# OF1_v1.net
KiCad netlist of a schematic drawn in EAGLE
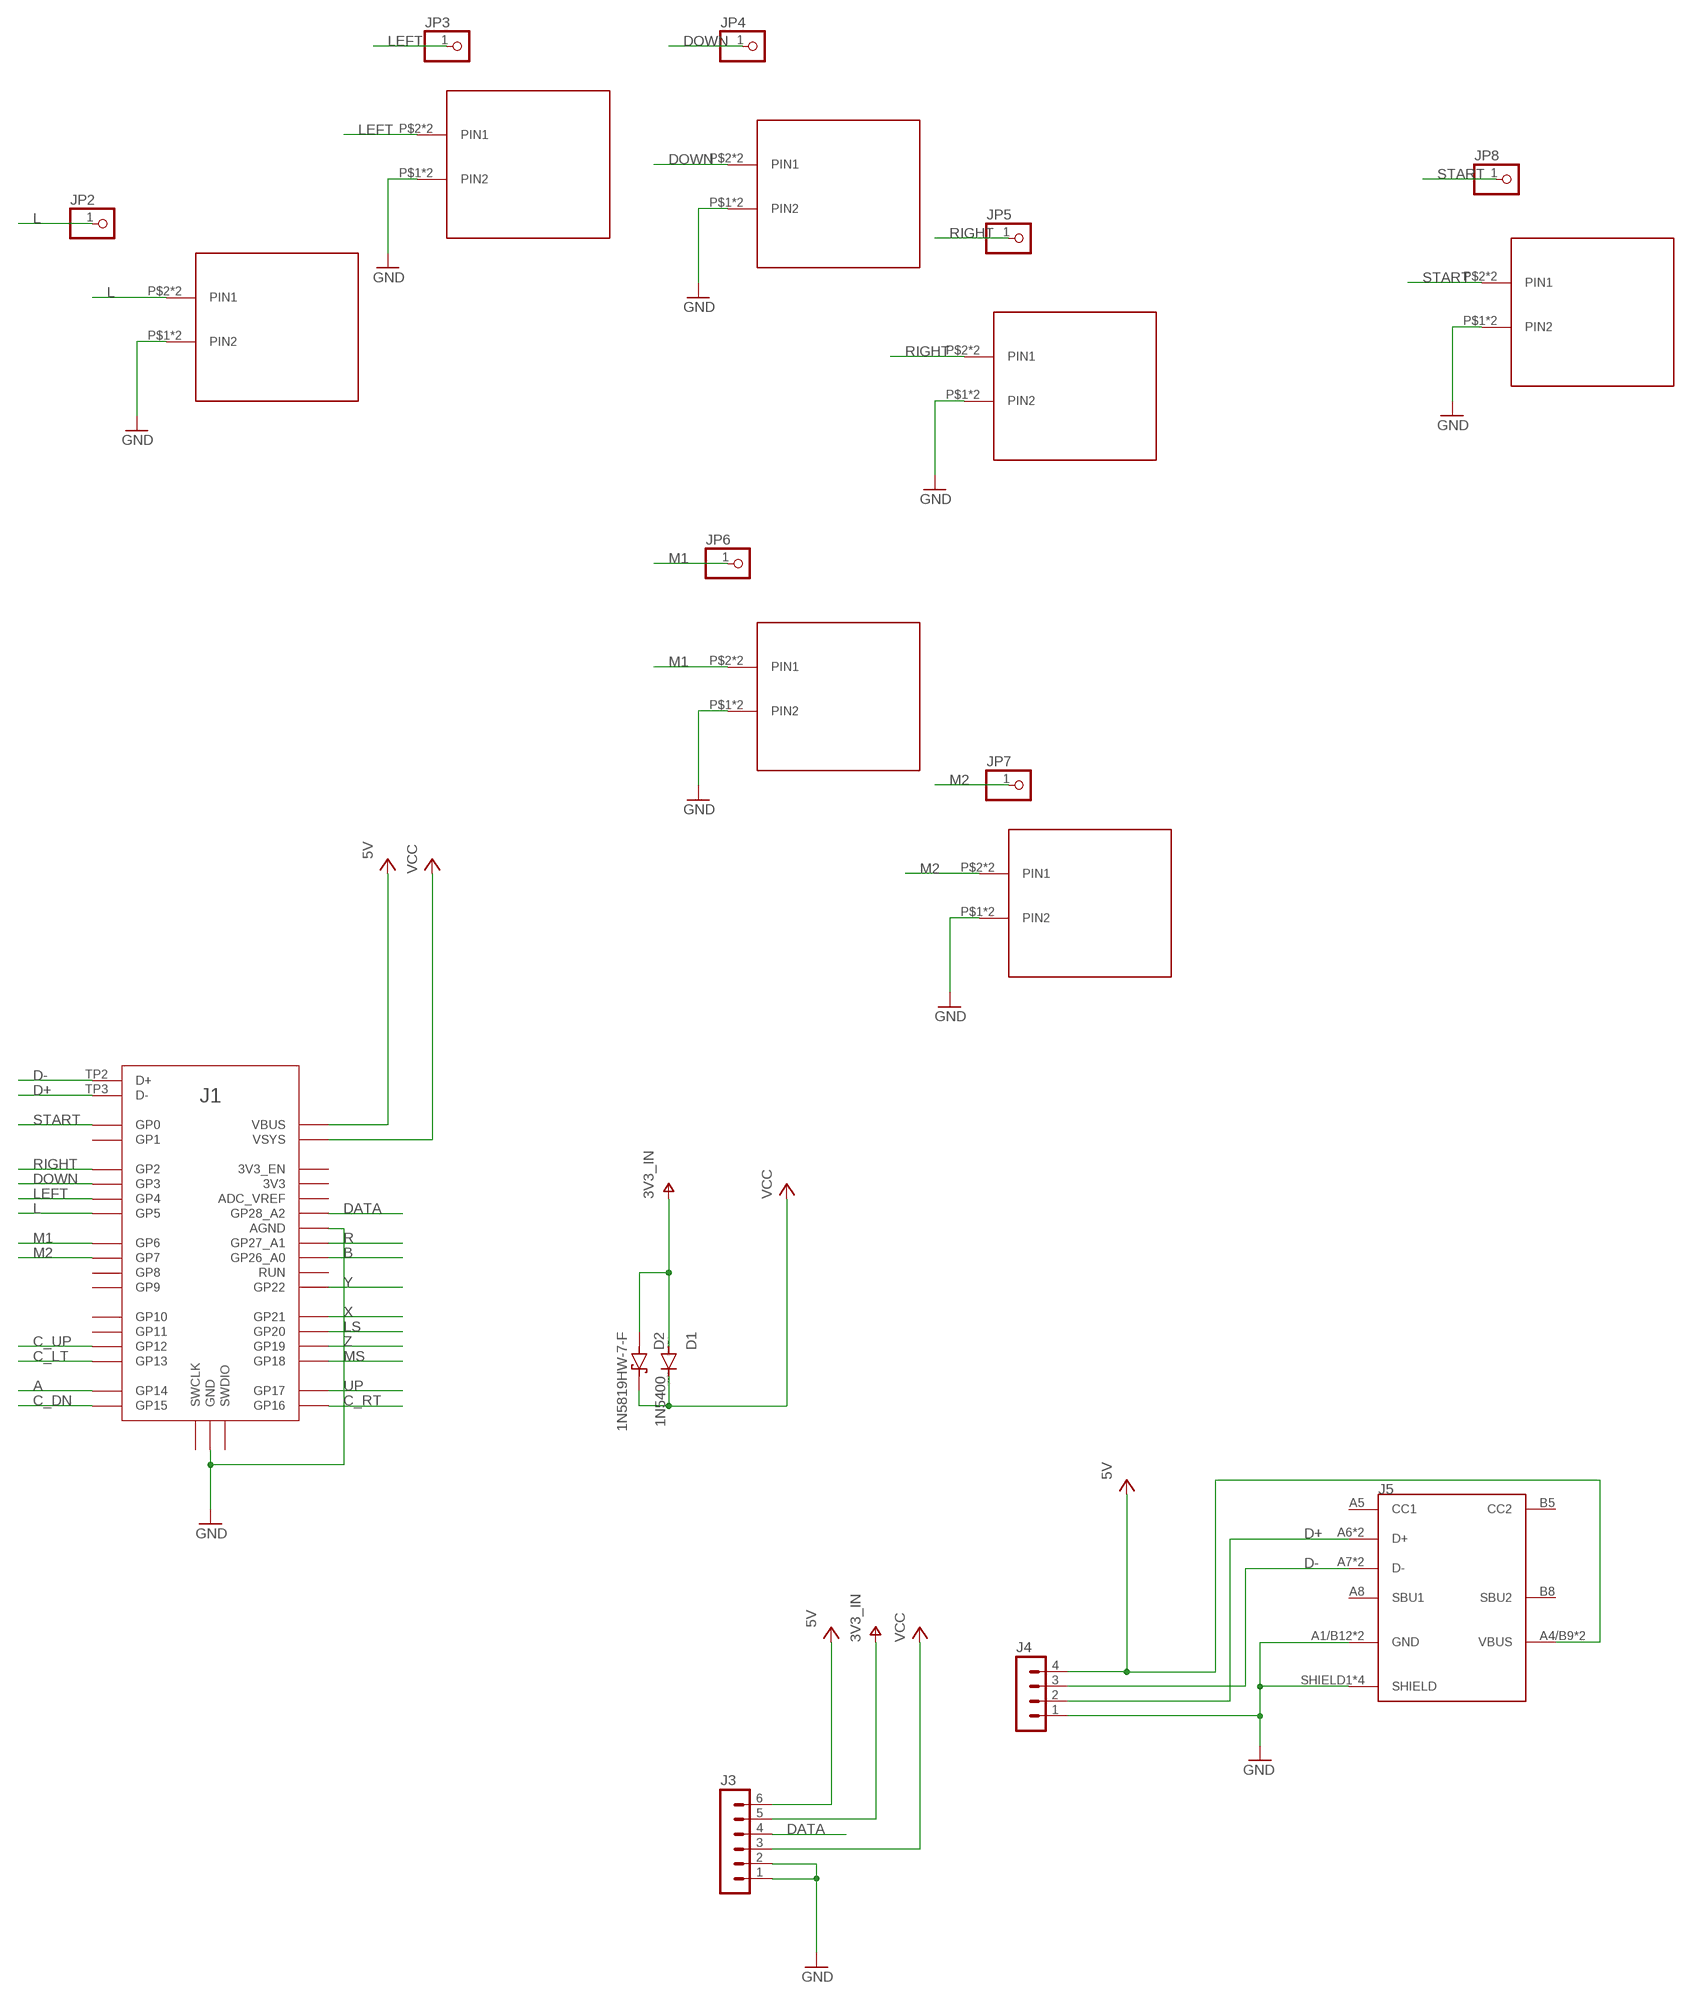
[diagram p0: schematic, sheet 1, part 1 of 2]
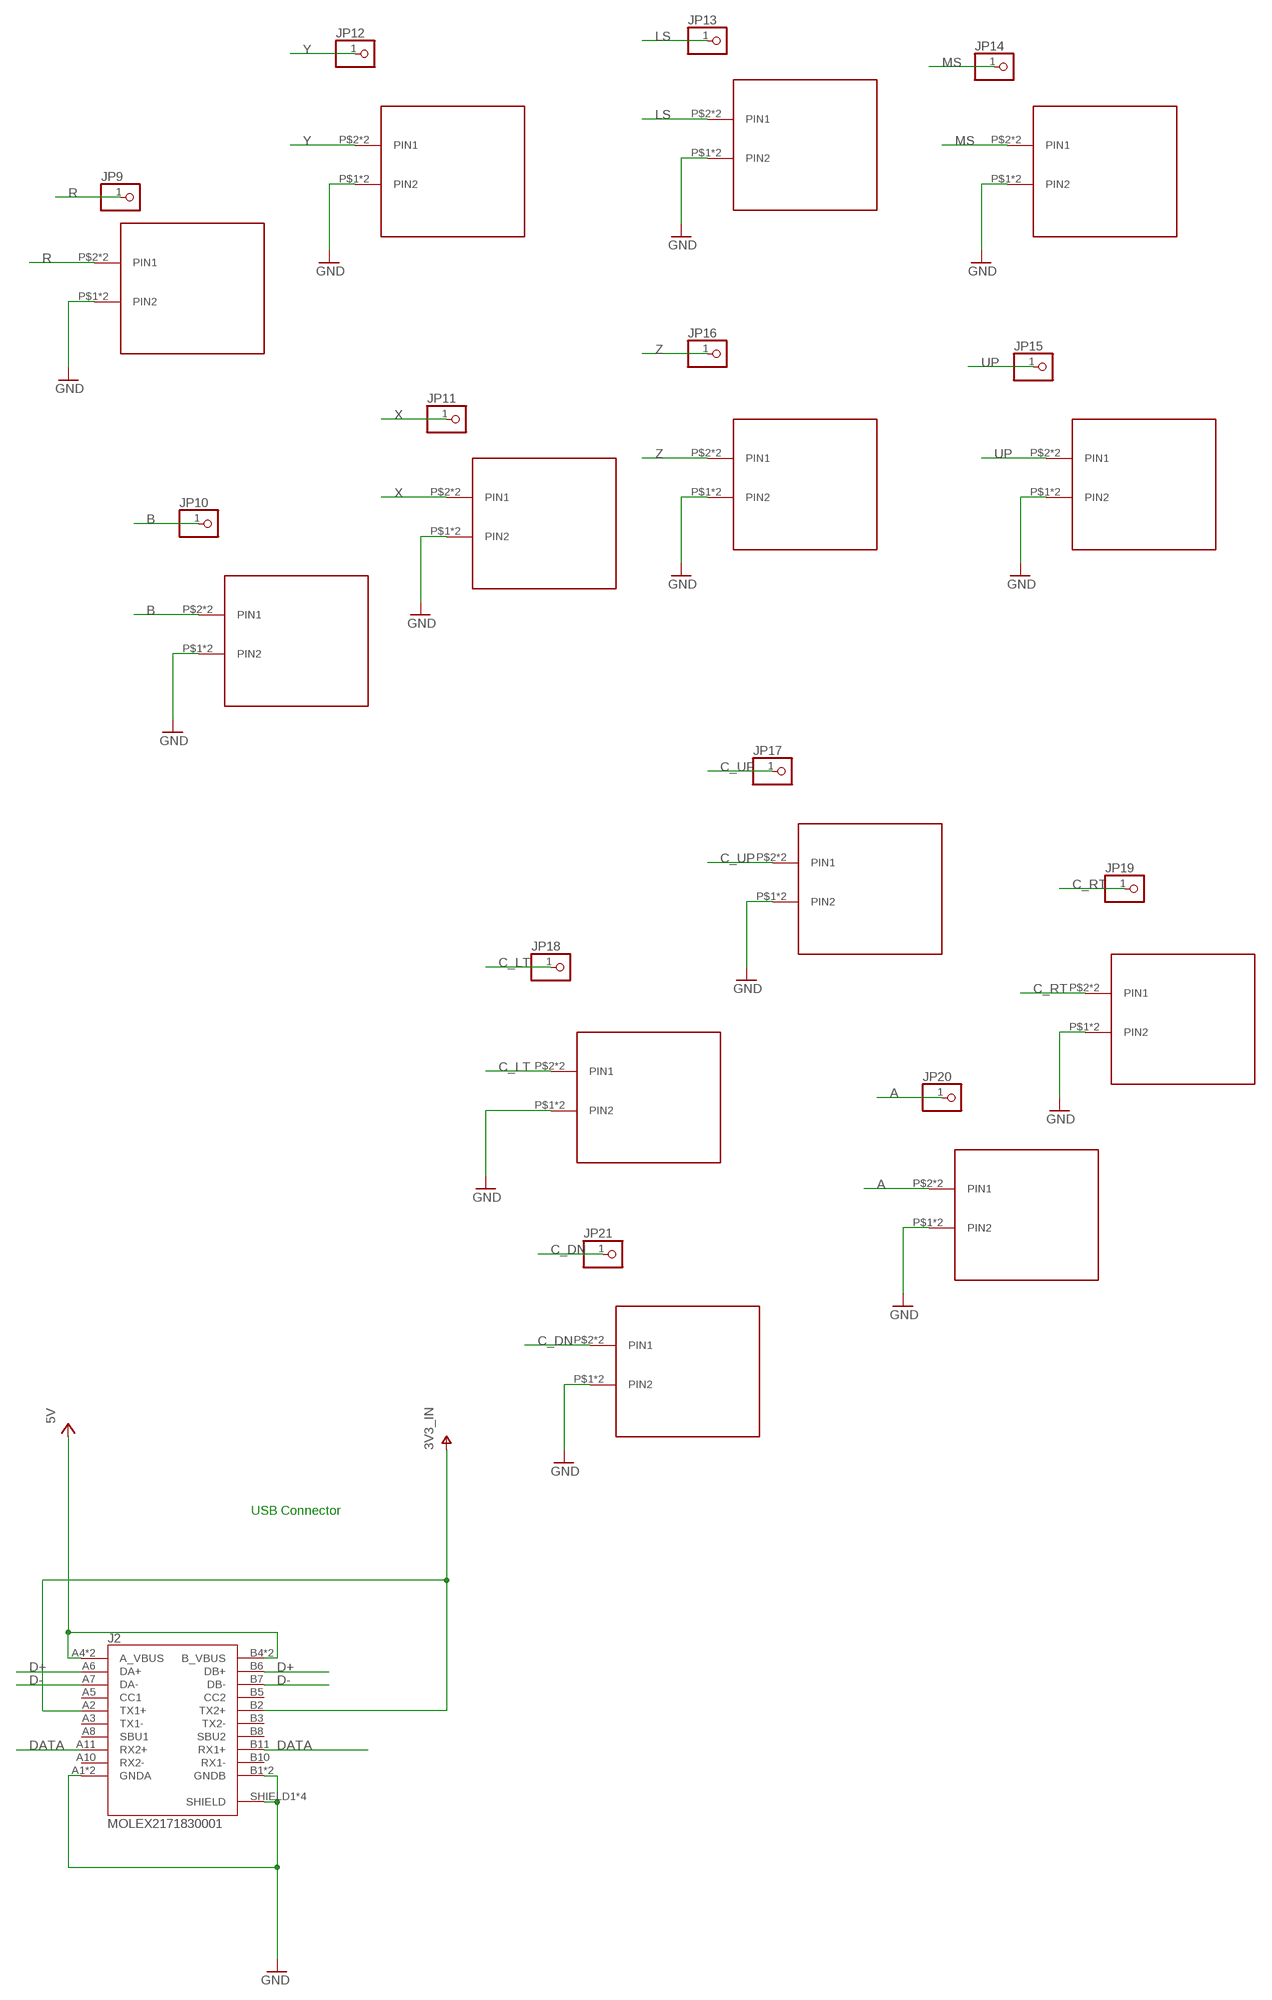
[diagram p1: schematic, sheet 1, part 2 of 2]

(export (version "E")
  (design (tool "Eeschema 10.0.6"))
  (components
    (comp (ref "D1")
      (value "1N5400")
      (footprint "eagle-import:DO201-15")
      (libsource (lib "eagle-import") (part "1N5400"))
    )
    (comp (ref "D2")
      (value "1N5819HW-7-F")
      (footprint "eagle-import:SOD3715X145N")
      (fields (field (name "MF") "Diodes Inc."))
      (libsource (lib "eagle-import") (part "1N5819HW-7-F"))
    )
    (comp (ref "J1")
      (value "RPI_PICO-TH")
      (footprint "eagle-import:RPI_PICO_TH")
      (libsource (lib "eagle-import") (part "RPI_PICO-TH"))
    )
    (comp (ref "J2")
      (value "MOLEX2171830001")
      (footprint "eagle-import:24P")
      (libsource (lib "eagle-import") (part "MOLEX2171830001"))
    )
    (comp (ref "J3")
      (value "MA06-1")
      (footprint "eagle-import:MA06-1")
      (libsource (lib "eagle-import") (part "MA06-1"))
    )
    (comp (ref "J4")
      (value "MA04-1")
      (footprint "eagle-import:MA04-1")
      (libsource (lib "eagle-import") (part "MA04-1"))
    )
    (comp (ref "J5")
      (value "GT-USB-7010ASV")
      (footprint "eagle-import:16P")
      (libsource (lib "eagle-import") (part "GT-USB-7010ASV"))
    )
    (comp (ref "JP2")
      (value "PINHD-1X1")
      (footprint "eagle-import:1X01")
      (libsource (lib "eagle-import") (part "PINHD-1X1"))
    )
    (comp (ref "JP3")
      (value "PINHD-1X1")
      (footprint "eagle-import:1X01")
      (libsource (lib "eagle-import") (part "PINHD-1X1"))
    )
    (comp (ref "JP4")
      (value "PINHD-1X1")
      (footprint "eagle-import:1X01")
      (libsource (lib "eagle-import") (part "PINHD-1X1"))
    )
    (comp (ref "JP5")
      (value "PINHD-1X1")
      (footprint "eagle-import:1X01")
      (libsource (lib "eagle-import") (part "PINHD-1X1"))
    )
    (comp (ref "JP6")
      (value "PINHD-1X1")
      (footprint "eagle-import:1X01")
      (libsource (lib "eagle-import") (part "PINHD-1X1"))
    )
    (comp (ref "JP7")
      (value "PINHD-1X1")
      (footprint "eagle-import:1X01")
      (libsource (lib "eagle-import") (part "PINHD-1X1"))
    )
    (comp (ref "JP8")
      (value "PINHD-1X1")
      (footprint "eagle-import:1X01")
      (libsource (lib "eagle-import") (part "PINHD-1X1"))
    )
    (comp (ref "JP9")
      (value "PINHD-1X1")
      (footprint "eagle-import:1X01")
      (libsource (lib "eagle-import") (part "PINHD-1X1"))
    )
    (comp (ref "JP10")
      (value "PINHD-1X1")
      (footprint "eagle-import:1X01")
      (libsource (lib "eagle-import") (part "PINHD-1X1"))
    )
    (comp (ref "JP11")
      (value "PINHD-1X1")
      (footprint "eagle-import:1X01")
      (libsource (lib "eagle-import") (part "PINHD-1X1"))
    )
    (comp (ref "JP12")
      (value "PINHD-1X1")
      (footprint "eagle-import:1X01")
      (libsource (lib "eagle-import") (part "PINHD-1X1"))
    )
    (comp (ref "JP13")
      (value "PINHD-1X1")
      (footprint "eagle-import:1X01")
      (libsource (lib "eagle-import") (part "PINHD-1X1"))
    )
    (comp (ref "JP14")
      (value "PINHD-1X1")
      (footprint "eagle-import:1X01")
      (libsource (lib "eagle-import") (part "PINHD-1X1"))
    )
    (comp (ref "JP15")
      (value "PINHD-1X1")
      (footprint "eagle-import:1X01")
      (libsource (lib "eagle-import") (part "PINHD-1X1"))
    )
    (comp (ref "JP16")
      (value "PINHD-1X1")
      (footprint "eagle-import:1X01")
      (libsource (lib "eagle-import") (part "PINHD-1X1"))
    )
    (comp (ref "JP17")
      (value "PINHD-1X1")
      (footprint "eagle-import:1X01")
      (libsource (lib "eagle-import") (part "PINHD-1X1"))
    )
    (comp (ref "JP18")
      (value "PINHD-1X1")
      (footprint "eagle-import:1X01")
      (libsource (lib "eagle-import") (part "PINHD-1X1"))
    )
    (comp (ref "JP19")
      (value "PINHD-1X1")
      (footprint "eagle-import:1X01")
      (libsource (lib "eagle-import") (part "PINHD-1X1"))
    )
    (comp (ref "JP20")
      (value "PINHD-1X1")
      (footprint "eagle-import:1X01")
      (libsource (lib "eagle-import") (part "PINHD-1X1"))
    )
    (comp (ref "JP21")
      (value "PINHD-1X1")
      (footprint "eagle-import:1X01")
      (libsource (lib "eagle-import") (part "PINHD-1X1"))
    )
    (comp (ref "U$1")
      (value "MX-B")
      (footprint "eagle-import:MX-BOTH")
      (libsource (lib "eagle-import") (part "MX-B"))
    )
    (comp (ref "U$2")
      (value "MX-B")
      (footprint "eagle-import:MX-BOTH")
      (libsource (lib "eagle-import") (part "MX-B"))
    )
    (comp (ref "U$4")
      (value "MX-B")
      (footprint "eagle-import:MX-BOTH")
      (libsource (lib "eagle-import") (part "MX-B"))
    )
    (comp (ref "U$5")
      (value "MX-B")
      (footprint "eagle-import:MX-BOTH")
      (libsource (lib "eagle-import") (part "MX-B"))
    )
    (comp (ref "U$6")
      (value "MX-B")
      (footprint "eagle-import:MX-BOTH")
      (libsource (lib "eagle-import") (part "MX-B"))
    )
    (comp (ref "U$7")
      (value "MX-B")
      (footprint "eagle-import:MX-BOTH")
      (libsource (lib "eagle-import") (part "MX-B"))
    )
    (comp (ref "U$8")
      (value "MX-B")
      (footprint "eagle-import:MX-BOTH")
      (libsource (lib "eagle-import") (part "MX-B"))
    )
    (comp (ref "U$9")
      (value "MX-B")
      (footprint "eagle-import:MX-BOTH")
      (libsource (lib "eagle-import") (part "MX-B"))
    )
    (comp (ref "U$10")
      (value "MX-B")
      (footprint "eagle-import:MX-BOTH")
      (libsource (lib "eagle-import") (part "MX-B"))
    )
    (comp (ref "U$11")
      (value "MX-B")
      (footprint "eagle-import:MX-BOTH")
      (libsource (lib "eagle-import") (part "MX-B"))
    )
    (comp (ref "U$12")
      (value "MX-B")
      (footprint "eagle-import:MX-BOTH")
      (libsource (lib "eagle-import") (part "MX-B"))
    )
    (comp (ref "U$13")
      (value "MX-B")
      (footprint "eagle-import:MX-BOTH")
      (libsource (lib "eagle-import") (part "MX-B"))
    )
    (comp (ref "U$14")
      (value "MX-B")
      (footprint "eagle-import:MX-BOTH")
      (libsource (lib "eagle-import") (part "MX-B"))
    )
    (comp (ref "U$15")
      (value "MX-B")
      (footprint "eagle-import:MX-BOTH")
      (libsource (lib "eagle-import") (part "MX-B"))
    )
    (comp (ref "U$16")
      (value "MX-B")
      (footprint "eagle-import:MX-BOTH")
      (libsource (lib "eagle-import") (part "MX-B"))
    )
    (comp (ref "U$17")
      (value "MX-B")
      (footprint "eagle-import:MX-BOTH")
      (libsource (lib "eagle-import") (part "MX-B"))
    )
    (comp (ref "U$18")
      (value "MX-B")
      (footprint "eagle-import:MX-BOTH")
      (libsource (lib "eagle-import") (part "MX-B"))
    )
    (comp (ref "U$19")
      (value "MX-B")
      (footprint "eagle-import:MX-BOTH")
      (libsource (lib "eagle-import") (part "MX-B"))
    )
    (comp (ref "U$20")
      (value "MX-B")
      (footprint "eagle-import:MX-BOTH")
      (libsource (lib "eagle-import") (part "MX-B"))
    )
    (comp (ref "U$21")
      (value "MX-B")
      (footprint "eagle-import:MX-BOTH")
      (libsource (lib "eagle-import") (part "MX-B"))
    )
  )
  (nets
    (net (code "1") (name "/A") (class "Default")
      (node (ref "J1") (pin "GP14") (pinfunction "GP14_GP14") (pintype "bidirectional"))
      (node (ref "JP20") (pin "1") (pinfunction "1_1") (pintype "passive"))
      (node (ref "U$20") (pin "P$2") (pinfunction "PIN1_P$2") (pintype "bidirectional"))
      (node (ref "U$20") (pin "P$3") (pinfunction "PIN1_P$3") (pintype "bidirectional"))
    )
    (net (code "2") (name "/B") (class "Default")
      (node (ref "J1") (pin "GP26_A0") (pinfunction "GP26_A0_GP26_A0") (pintype "bidirectional"))
      (node (ref "JP10") (pin "1") (pinfunction "1_1") (pintype "passive"))
      (node (ref "U$13") (pin "P$2") (pinfunction "PIN1_P$2") (pintype "bidirectional"))
      (node (ref "U$13") (pin "P$3") (pinfunction "PIN1_P$3") (pintype "bidirectional"))
    )
    (net (code "3") (name "/C_DN") (class "Default")
      (node (ref "J1") (pin "GP15") (pinfunction "GP15_GP15") (pintype "bidirectional"))
      (node (ref "JP21") (pin "1") (pinfunction "1_1") (pintype "passive"))
      (node (ref "U$21") (pin "P$2") (pinfunction "PIN1_P$2") (pintype "bidirectional"))
      (node (ref "U$21") (pin "P$3") (pinfunction "PIN1_P$3") (pintype "bidirectional"))
    )
    (net (code "4") (name "/C_LT") (class "Default")
      (node (ref "J1") (pin "GP13") (pinfunction "GP13_GP13") (pintype "bidirectional"))
      (node (ref "JP18") (pin "1") (pinfunction "1_1") (pintype "passive"))
      (node (ref "U$18") (pin "P$2") (pinfunction "PIN1_P$2") (pintype "bidirectional"))
      (node (ref "U$18") (pin "P$3") (pinfunction "PIN1_P$3") (pintype "bidirectional"))
    )
    (net (code "5") (name "/C_RT") (class "Default")
      (node (ref "J1") (pin "GP16") (pinfunction "GP16_GP16") (pintype "bidirectional"))
      (node (ref "JP19") (pin "1") (pinfunction "1_1") (pintype "passive"))
      (node (ref "U$19") (pin "P$2") (pinfunction "PIN1_P$2") (pintype "bidirectional"))
      (node (ref "U$19") (pin "P$3") (pinfunction "PIN1_P$3") (pintype "bidirectional"))
    )
    (net (code "6") (name "/C_UP") (class "Default")
      (node (ref "J1") (pin "GP12") (pinfunction "GP12_GP12") (pintype "bidirectional"))
      (node (ref "JP17") (pin "1") (pinfunction "1_1") (pintype "passive"))
      (node (ref "U$17") (pin "P$2") (pinfunction "PIN1_P$2") (pintype "bidirectional"))
      (node (ref "U$17") (pin "P$3") (pinfunction "PIN1_P$3") (pintype "bidirectional"))
    )
    (net (code "7") (name "/D+") (class "Default")
      (node (ref "J1") (pin "TP3") (pinfunction "D-_TP3") (pintype "bidirectional"))
      (node (ref "J2") (pin "A6") (pinfunction "DA+_A6") (pintype "passive"))
      (node (ref "J2") (pin "B6") (pinfunction "DB+_B6") (pintype "passive"))
      (node (ref "J4") (pin "2") (pinfunction "2_2") (pintype "passive"))
      (node (ref "J5") (pin "A6") (pinfunction "D+_A6") (pintype "bidirectional"))
      (node (ref "J5") (pin "B6") (pinfunction "D+_B6") (pintype "bidirectional"))
    )
    (net (code "8") (name "/D-") (class "Default")
      (node (ref "J1") (pin "TP2") (pinfunction "D+_TP2") (pintype "bidirectional"))
      (node (ref "J2") (pin "A7") (pinfunction "DA-_A7") (pintype "passive"))
      (node (ref "J2") (pin "B7") (pinfunction "DB-_B7") (pintype "passive"))
      (node (ref "J4") (pin "3") (pinfunction "3_3") (pintype "passive"))
      (node (ref "J5") (pin "A7") (pinfunction "D-_A7") (pintype "bidirectional"))
      (node (ref "J5") (pin "B7") (pinfunction "D-_B7") (pintype "bidirectional"))
    )
    (net (code "9") (name "/DATA") (class "Default")
      (node (ref "J1") (pin "GP28_A2") (pinfunction "GP28_A2_GP28_A2") (pintype "bidirectional"))
      (node (ref "J2") (pin "A11") (pinfunction "RX2+_A11") (pintype "passive"))
      (node (ref "J2") (pin "B11") (pinfunction "RX1+_B11") (pintype "passive"))
      (node (ref "J3") (pin "4") (pinfunction "4_4") (pintype "passive"))
    )
    (net (code "10") (name "/DOWN") (class "Default")
      (node (ref "J1") (pin "GP3") (pinfunction "GP3_GP3") (pintype "bidirectional"))
      (node (ref "JP4") (pin "1") (pinfunction "1_1") (pintype "passive"))
      (node (ref "U$4") (pin "P$2") (pinfunction "PIN1_P$2") (pintype "bidirectional"))
      (node (ref "U$4") (pin "P$3") (pinfunction "PIN1_P$3") (pintype "bidirectional"))
    )
    (net (code "11") (name "/L") (class "Default")
      (node (ref "J1") (pin "GP5") (pinfunction "GP5_GP5") (pintype "bidirectional"))
      (node (ref "JP2") (pin "1") (pinfunction "1_1") (pintype "passive"))
      (node (ref "U$1") (pin "P$2") (pinfunction "PIN1_P$2") (pintype "bidirectional"))
      (node (ref "U$1") (pin "P$3") (pinfunction "PIN1_P$3") (pintype "bidirectional"))
    )
    (net (code "12") (name "/LEFT") (class "Default")
      (node (ref "J1") (pin "GP4") (pinfunction "GP4_GP4") (pintype "bidirectional"))
      (node (ref "JP3") (pin "1") (pinfunction "1_1") (pintype "passive"))
      (node (ref "U$2") (pin "P$2") (pinfunction "PIN1_P$2") (pintype "bidirectional"))
      (node (ref "U$2") (pin "P$3") (pinfunction "PIN1_P$3") (pintype "bidirectional"))
    )
    (net (code "13") (name "/LS") (class "Default")
      (node (ref "J1") (pin "GP20") (pinfunction "GP20_GP20") (pintype "bidirectional"))
      (node (ref "JP13") (pin "1") (pinfunction "1_1") (pintype "passive"))
      (node (ref "U$11") (pin "P$2") (pinfunction "PIN1_P$2") (pintype "bidirectional"))
      (node (ref "U$11") (pin "P$3") (pinfunction "PIN1_P$3") (pintype "bidirectional"))
    )
    (net (code "14") (name "/M1") (class "Default")
      (node (ref "J1") (pin "GP6") (pinfunction "GP6_GP6") (pintype "bidirectional"))
      (node (ref "JP6") (pin "1") (pinfunction "1_1") (pintype "passive"))
      (node (ref "U$6") (pin "P$2") (pinfunction "PIN1_P$2") (pintype "bidirectional"))
      (node (ref "U$6") (pin "P$3") (pinfunction "PIN1_P$3") (pintype "bidirectional"))
    )
    (net (code "15") (name "/M2") (class "Default")
      (node (ref "J1") (pin "GP7") (pinfunction "GP7_GP7") (pintype "bidirectional"))
      (node (ref "JP7") (pin "1") (pinfunction "1_1") (pintype "passive"))
      (node (ref "U$7") (pin "P$2") (pinfunction "PIN1_P$2") (pintype "bidirectional"))
      (node (ref "U$7") (pin "P$3") (pinfunction "PIN1_P$3") (pintype "bidirectional"))
    )
    (net (code "16") (name "/MS") (class "Default")
      (node (ref "J1") (pin "GP18") (pinfunction "GP18_GP18") (pintype "bidirectional"))
      (node (ref "JP14") (pin "1") (pinfunction "1_1") (pintype "passive"))
      (node (ref "U$12") (pin "P$2") (pinfunction "PIN1_P$2") (pintype "bidirectional"))
      (node (ref "U$12") (pin "P$3") (pinfunction "PIN1_P$3") (pintype "bidirectional"))
    )
    (net (code "17") (name "/R") (class "Default")
      (node (ref "J1") (pin "GP27_A1") (pinfunction "GP27_A1_GP27_A1") (pintype "bidirectional"))
      (node (ref "JP9") (pin "1") (pinfunction "1_1") (pintype "passive"))
      (node (ref "U$9") (pin "P$2") (pinfunction "PIN1_P$2") (pintype "bidirectional"))
      (node (ref "U$9") (pin "P$3") (pinfunction "PIN1_P$3") (pintype "bidirectional"))
    )
    (net (code "18") (name "/RIGHT") (class "Default")
      (node (ref "J1") (pin "GP2") (pinfunction "GP2_GP2") (pintype "bidirectional"))
      (node (ref "JP5") (pin "1") (pinfunction "1_1") (pintype "passive"))
      (node (ref "U$5") (pin "P$2") (pinfunction "PIN1_P$2") (pintype "bidirectional"))
      (node (ref "U$5") (pin "P$3") (pinfunction "PIN1_P$3") (pintype "bidirectional"))
    )
    (net (code "19") (name "/START") (class "Default")
      (node (ref "J1") (pin "GP0") (pinfunction "GP0_GP0") (pintype "bidirectional"))
      (node (ref "JP8") (pin "1") (pinfunction "1_1") (pintype "passive"))
      (node (ref "U$8") (pin "P$2") (pinfunction "PIN1_P$2") (pintype "bidirectional"))
      (node (ref "U$8") (pin "P$3") (pinfunction "PIN1_P$3") (pintype "bidirectional"))
    )
    (net (code "20") (name "/UP") (class "Default")
      (node (ref "J1") (pin "GP17") (pinfunction "GP17_GP17") (pintype "bidirectional"))
      (node (ref "JP15") (pin "1") (pinfunction "1_1") (pintype "passive"))
      (node (ref "U$16") (pin "P$2") (pinfunction "PIN1_P$2") (pintype "bidirectional"))
      (node (ref "U$16") (pin "P$3") (pinfunction "PIN1_P$3") (pintype "bidirectional"))
    )
    (net (code "21") (name "/X") (class "Default")
      (node (ref "J1") (pin "GP21") (pinfunction "GP21_GP21") (pintype "bidirectional"))
      (node (ref "JP11") (pin "1") (pinfunction "1_1") (pintype "passive"))
      (node (ref "U$14") (pin "P$2") (pinfunction "PIN1_P$2") (pintype "bidirectional"))
      (node (ref "U$14") (pin "P$3") (pinfunction "PIN1_P$3") (pintype "bidirectional"))
    )
    (net (code "22") (name "/Y") (class "Default")
      (node (ref "J1") (pin "GP22") (pinfunction "GP22_GP22") (pintype "bidirectional"))
      (node (ref "JP12") (pin "1") (pinfunction "1_1") (pintype "passive"))
      (node (ref "U$10") (pin "P$2") (pinfunction "PIN1_P$2") (pintype "bidirectional"))
      (node (ref "U$10") (pin "P$3") (pinfunction "PIN1_P$3") (pintype "bidirectional"))
    )
    (net (code "23") (name "/Z") (class "Default")
      (node (ref "J1") (pin "GP19") (pinfunction "GP19_GP19") (pintype "bidirectional"))
      (node (ref "JP16") (pin "1") (pinfunction "1_1") (pintype "passive"))
      (node (ref "U$15") (pin "P$2") (pinfunction "PIN1_P$2") (pintype "bidirectional"))
      (node (ref "U$15") (pin "P$3") (pinfunction "PIN1_P$3") (pintype "bidirectional"))
    )
    (net (code "24") (name "3V3_IN") (class "Default")
      (node (ref "D1") (pin "A") (pinfunction "A_A") (pintype "passive"))
      (node (ref "D2") (pin "A") (pinfunction "A_A") (pintype "passive"))
      (node (ref "J2") (pin "A2") (pinfunction "TX1+_A2") (pintype "passive"))
      (node (ref "J2") (pin "B2") (pinfunction "TX2+_B2") (pintype "passive"))
      (node (ref "J3") (pin "5") (pinfunction "5_5") (pintype "passive"))
    )
    (net (code "25") (name "5V") (class "Default")
      (node (ref "J1") (pin "VBUS") (pinfunction "VBUS_VBUS") (pintype "bidirectional"))
      (node (ref "J2") (pin "A4") (pinfunction "A_VBUS_A4") (pintype "passive"))
      (node (ref "J2") (pin "A9") (pinfunction "A_VBUS_A9") (pintype "passive"))
      (node (ref "J2") (pin "B4") (pinfunction "B_VBUS_B4") (pintype "passive"))
      (node (ref "J2") (pin "B9") (pinfunction "B_VBUS_B9") (pintype "passive"))
      (node (ref "J3") (pin "6") (pinfunction "6_6") (pintype "passive"))
      (node (ref "J4") (pin "4") (pinfunction "4_4") (pintype "passive"))
      (node (ref "J5") (pin "A4/B9") (pinfunction "VBUS_A4/B9") (pintype "bidirectional"))
      (node (ref "J5") (pin "B4/A9") (pinfunction "VBUS_B4/A9") (pintype "bidirectional"))
    )
    (net (code "26") (name "GND") (class "Default")
      (node (ref "J1") (pin "AGND") (pinfunction "AGND_AGND") (pintype "bidirectional"))
      (node (ref "J1") (pin "GND@1") (pinfunction "GND_GND@1") (pintype "bidirectional"))
      (node (ref "J1") (pin "GND@2") (pinfunction "GND_GND@2") (pintype "bidirectional"))
      (node (ref "J1") (pin "GND@3") (pinfunction "GND_GND@3") (pintype "bidirectional"))
      (node (ref "J1") (pin "GND@4") (pinfunction "GND_GND@4") (pintype "bidirectional"))
      (node (ref "J1") (pin "GND@5") (pinfunction "GND_GND@5") (pintype "bidirectional"))
      (node (ref "J1") (pin "GND@6") (pinfunction "GND_GND@6") (pintype "bidirectional"))
      (node (ref "J1") (pin "GND@7") (pinfunction "GND_GND@7") (pintype "bidirectional"))
      (node (ref "J1") (pin "GND@8") (pinfunction "GND_GND@8") (pintype "bidirectional"))
      (node (ref "J2") (pin "A1") (pinfunction "GNDA_A1") (pintype "passive"))
      (node (ref "J2") (pin "A12") (pinfunction "GNDA_A12") (pintype "passive"))
      (node (ref "J2") (pin "B1") (pinfunction "GNDB_B1") (pintype "passive"))
      (node (ref "J2") (pin "B12") (pinfunction "GNDB_B12") (pintype "passive"))
      (node (ref "J2") (pin "SHIELD1") (pinfunction "SHIELD_SHIELD1") (pintype "passive"))
      (node (ref "J2") (pin "SHIELD2") (pinfunction "SHIELD_SHIELD2") (pintype "passive"))
      (node (ref "J2") (pin "SHIELD3") (pinfunction "SHIELD_SHIELD3") (pintype "passive"))
      (node (ref "J2") (pin "SHIELD4") (pinfunction "SHIELD_SHIELD4") (pintype "passive"))
      (node (ref "J3") (pin "1") (pinfunction "1_1") (pintype "passive"))
      (node (ref "J3") (pin "2") (pinfunction "2_2") (pintype "passive"))
      (node (ref "J4") (pin "1") (pinfunction "1_1") (pintype "passive"))
      (node (ref "J5") (pin "A1/B12") (pinfunction "GND_A1/B12") (pintype "bidirectional"))
      (node (ref "J5") (pin "B1/A12") (pinfunction "GND_B1/A12") (pintype "bidirectional"))
      (node (ref "J5") (pin "SHIELD1") (pinfunction "SHIELD_SHIELD1") (pintype "bidirectional"))
      (node (ref "J5") (pin "SHIELD2") (pinfunction "SHIELD_SHIELD2") (pintype "bidirectional"))
      (node (ref "J5") (pin "SHIELD3") (pinfunction "SHIELD_SHIELD3") (pintype "bidirectional"))
      (node (ref "J5") (pin "SHIELD4") (pinfunction "SHIELD_SHIELD4") (pintype "bidirectional"))
      (node (ref "U$1") (pin "P$1") (pinfunction "PIN2_P$1") (pintype "bidirectional"))
      (node (ref "U$1") (pin "P$4") (pinfunction "PIN2_P$4") (pintype "bidirectional"))
      (node (ref "U$10") (pin "P$1") (pinfunction "PIN2_P$1") (pintype "bidirectional"))
      (node (ref "U$10") (pin "P$4") (pinfunction "PIN2_P$4") (pintype "bidirectional"))
      (node (ref "U$11") (pin "P$1") (pinfunction "PIN2_P$1") (pintype "bidirectional"))
      (node (ref "U$11") (pin "P$4") (pinfunction "PIN2_P$4") (pintype "bidirectional"))
      (node (ref "U$12") (pin "P$1") (pinfunction "PIN2_P$1") (pintype "bidirectional"))
      (node (ref "U$12") (pin "P$4") (pinfunction "PIN2_P$4") (pintype "bidirectional"))
      (node (ref "U$13") (pin "P$1") (pinfunction "PIN2_P$1") (pintype "bidirectional"))
      (node (ref "U$13") (pin "P$4") (pinfunction "PIN2_P$4") (pintype "bidirectional"))
      (node (ref "U$14") (pin "P$1") (pinfunction "PIN2_P$1") (pintype "bidirectional"))
      (node (ref "U$14") (pin "P$4") (pinfunction "PIN2_P$4") (pintype "bidirectional"))
      (node (ref "U$15") (pin "P$1") (pinfunction "PIN2_P$1") (pintype "bidirectional"))
      (node (ref "U$15") (pin "P$4") (pinfunction "PIN2_P$4") (pintype "bidirectional"))
      (node (ref "U$16") (pin "P$1") (pinfunction "PIN2_P$1") (pintype "bidirectional"))
      (node (ref "U$16") (pin "P$4") (pinfunction "PIN2_P$4") (pintype "bidirectional"))
      (node (ref "U$17") (pin "P$1") (pinfunction "PIN2_P$1") (pintype "bidirectional"))
      (node (ref "U$17") (pin "P$4") (pinfunction "PIN2_P$4") (pintype "bidirectional"))
      (node (ref "U$18") (pin "P$1") (pinfunction "PIN2_P$1") (pintype "bidirectional"))
      (node (ref "U$18") (pin "P$4") (pinfunction "PIN2_P$4") (pintype "bidirectional"))
      (node (ref "U$19") (pin "P$1") (pinfunction "PIN2_P$1") (pintype "bidirectional"))
      (node (ref "U$19") (pin "P$4") (pinfunction "PIN2_P$4") (pintype "bidirectional"))
      (node (ref "U$2") (pin "P$1") (pinfunction "PIN2_P$1") (pintype "bidirectional"))
      (node (ref "U$2") (pin "P$4") (pinfunction "PIN2_P$4") (pintype "bidirectional"))
      (node (ref "U$20") (pin "P$1") (pinfunction "PIN2_P$1") (pintype "bidirectional"))
      (node (ref "U$20") (pin "P$4") (pinfunction "PIN2_P$4") (pintype "bidirectional"))
      (node (ref "U$21") (pin "P$1") (pinfunction "PIN2_P$1") (pintype "bidirectional"))
      (node (ref "U$21") (pin "P$4") (pinfunction "PIN2_P$4") (pintype "bidirectional"))
      (node (ref "U$4") (pin "P$1") (pinfunction "PIN2_P$1") (pintype "bidirectional"))
      (node (ref "U$4") (pin "P$4") (pinfunction "PIN2_P$4") (pintype "bidirectional"))
      (node (ref "U$5") (pin "P$1") (pinfunction "PIN2_P$1") (pintype "bidirectional"))
      (node (ref "U$5") (pin "P$4") (pinfunction "PIN2_P$4") (pintype "bidirectional"))
      (node (ref "U$6") (pin "P$1") (pinfunction "PIN2_P$1") (pintype "bidirectional"))
      (node (ref "U$6") (pin "P$4") (pinfunction "PIN2_P$4") (pintype "bidirectional"))
      (node (ref "U$7") (pin "P$1") (pinfunction "PIN2_P$1") (pintype "bidirectional"))
      (node (ref "U$7") (pin "P$4") (pinfunction "PIN2_P$4") (pintype "bidirectional"))
      (node (ref "U$8") (pin "P$1") (pinfunction "PIN2_P$1") (pintype "bidirectional"))
      (node (ref "U$8") (pin "P$4") (pinfunction "PIN2_P$4") (pintype "bidirectional"))
      (node (ref "U$9") (pin "P$1") (pinfunction "PIN2_P$1") (pintype "bidirectional"))
      (node (ref "U$9") (pin "P$4") (pinfunction "PIN2_P$4") (pintype "bidirectional"))
    )
    (net (code "27") (name "VCC") (class "Default")
      (node (ref "D1") (pin "C") (pinfunction "C_C") (pintype "passive"))
      (node (ref "D2") (pin "C") (pinfunction "K_C") (pintype "passive"))
      (node (ref "J1") (pin "VSYS") (pinfunction "VSYS_VSYS") (pintype "bidirectional"))
      (node (ref "J3") (pin "3") (pinfunction "3_3") (pintype "passive"))
    )
    (net (code "28") (name "unconnected-(J1-Pad3V3)") (class "Default")
      (node (ref "J1") (pin "3V3") (pinfunction "3V3_3V3") (pintype "bidirectional"))
    )
    (net (code "29") (name "unconnected-(J1-Pad3V3_EN)") (class "Default")
      (node (ref "J1") (pin "3V3_EN") (pinfunction "3V3_EN_3V3_EN") (pintype "bidirectional"))
    )
    (net (code "30") (name "unconnected-(J1-PadADC_VREF)") (class "Default")
      (node (ref "J1") (pin "ADC_VREF") (pinfunction "ADC_VREF_ADC_VREF") (pintype "bidirectional"))
    )
    (net (code "31") (name "unconnected-(J1-PadGP1)") (class "Default")
      (node (ref "J1") (pin "GP1") (pinfunction "GP1_GP1") (pintype "bidirectional"))
    )
    (net (code "32") (name "unconnected-(J1-PadGP8)") (class "Default")
      (node (ref "J1") (pin "GP8") (pinfunction "GP8_GP8") (pintype "bidirectional"))
    )
    (net (code "33") (name "unconnected-(J1-PadGP9)") (class "Default")
      (node (ref "J1") (pin "GP9") (pinfunction "GP9_GP9") (pintype "bidirectional"))
    )
    (net (code "34") (name "unconnected-(J1-PadGP10)") (class "Default")
      (node (ref "J1") (pin "GP10") (pinfunction "GP10_GP10") (pintype "bidirectional"))
    )
    (net (code "35") (name "unconnected-(J1-PadGP11)") (class "Default")
      (node (ref "J1") (pin "GP11") (pinfunction "GP11_GP11") (pintype "bidirectional"))
    )
    (net (code "36") (name "unconnected-(J1-PadRUN)") (class "Default")
      (node (ref "J1") (pin "RUN") (pinfunction "RUN_RUN") (pintype "bidirectional"))
    )
    (net (code "37") (name "unconnected-(J1-PadSWCLK)") (class "Default")
      (node (ref "J1") (pin "SWCLK") (pinfunction "SWCLK_SWCLK") (pintype "bidirectional"))
    )
    (net (code "38") (name "unconnected-(J1-PadSWDIO)") (class "Default")
      (node (ref "J1") (pin "SWDIO") (pinfunction "SWDIO_SWDIO") (pintype "bidirectional"))
    )
    (net (code "39") (name "unconnected-(J2-CC1-PadA5)") (class "Default")
      (node (ref "J2") (pin "A5") (pinfunction "CC1_A5") (pintype "passive"))
    )
    (net (code "40") (name "unconnected-(J2-CC2-PadB5)") (class "Default")
      (node (ref "J2") (pin "B5") (pinfunction "CC2_B5") (pintype "passive"))
    )
    (net (code "41") (name "unconnected-(J2-RX1--PadB10)") (class "Default")
      (node (ref "J2") (pin "B10") (pinfunction "RX1-_B10") (pintype "passive"))
    )
    (net (code "42") (name "unconnected-(J2-RX2--PadA10)") (class "Default")
      (node (ref "J2") (pin "A10") (pinfunction "RX2-_A10") (pintype "passive"))
    )
    (net (code "43") (name "unconnected-(J2-SBU1-PadA8)") (class "Default")
      (node (ref "J2") (pin "A8") (pinfunction "SBU1_A8") (pintype "passive"))
    )
    (net (code "44") (name "unconnected-(J2-SBU2-PadB8)") (class "Default")
      (node (ref "J2") (pin "B8") (pinfunction "SBU2_B8") (pintype "passive"))
    )
    (net (code "45") (name "unconnected-(J2-TX1--PadA3)") (class "Default")
      (node (ref "J2") (pin "A3") (pinfunction "TX1-_A3") (pintype "passive"))
    )
    (net (code "46") (name "unconnected-(J2-TX2--PadB3)") (class "Default")
      (node (ref "J2") (pin "B3") (pinfunction "TX2-_B3") (pintype "passive"))
    )
    (net (code "47") (name "unconnected-(J5-CC1-PadA5)") (class "Default")
      (node (ref "J5") (pin "A5") (pinfunction "CC1_A5") (pintype "bidirectional"))
    )
    (net (code "48") (name "unconnected-(J5-CC2-PadB5)") (class "Default")
      (node (ref "J5") (pin "B5") (pinfunction "CC2_B5") (pintype "bidirectional"))
    )
    (net (code "49") (name "unconnected-(J5-SBU1-PadA8)") (class "Default")
      (node (ref "J5") (pin "A8") (pinfunction "SBU1_A8") (pintype "bidirectional"))
    )
    (net (code "50") (name "unconnected-(J5-SBU2-PadB8)") (class "Default")
      (node (ref "J5") (pin "B8") (pinfunction "SBU2_B8") (pintype "bidirectional"))
    )
  )
)
